# ai_robocarpi_linesensor.net
KiCad netlist of a schematic drawn in EAGLE
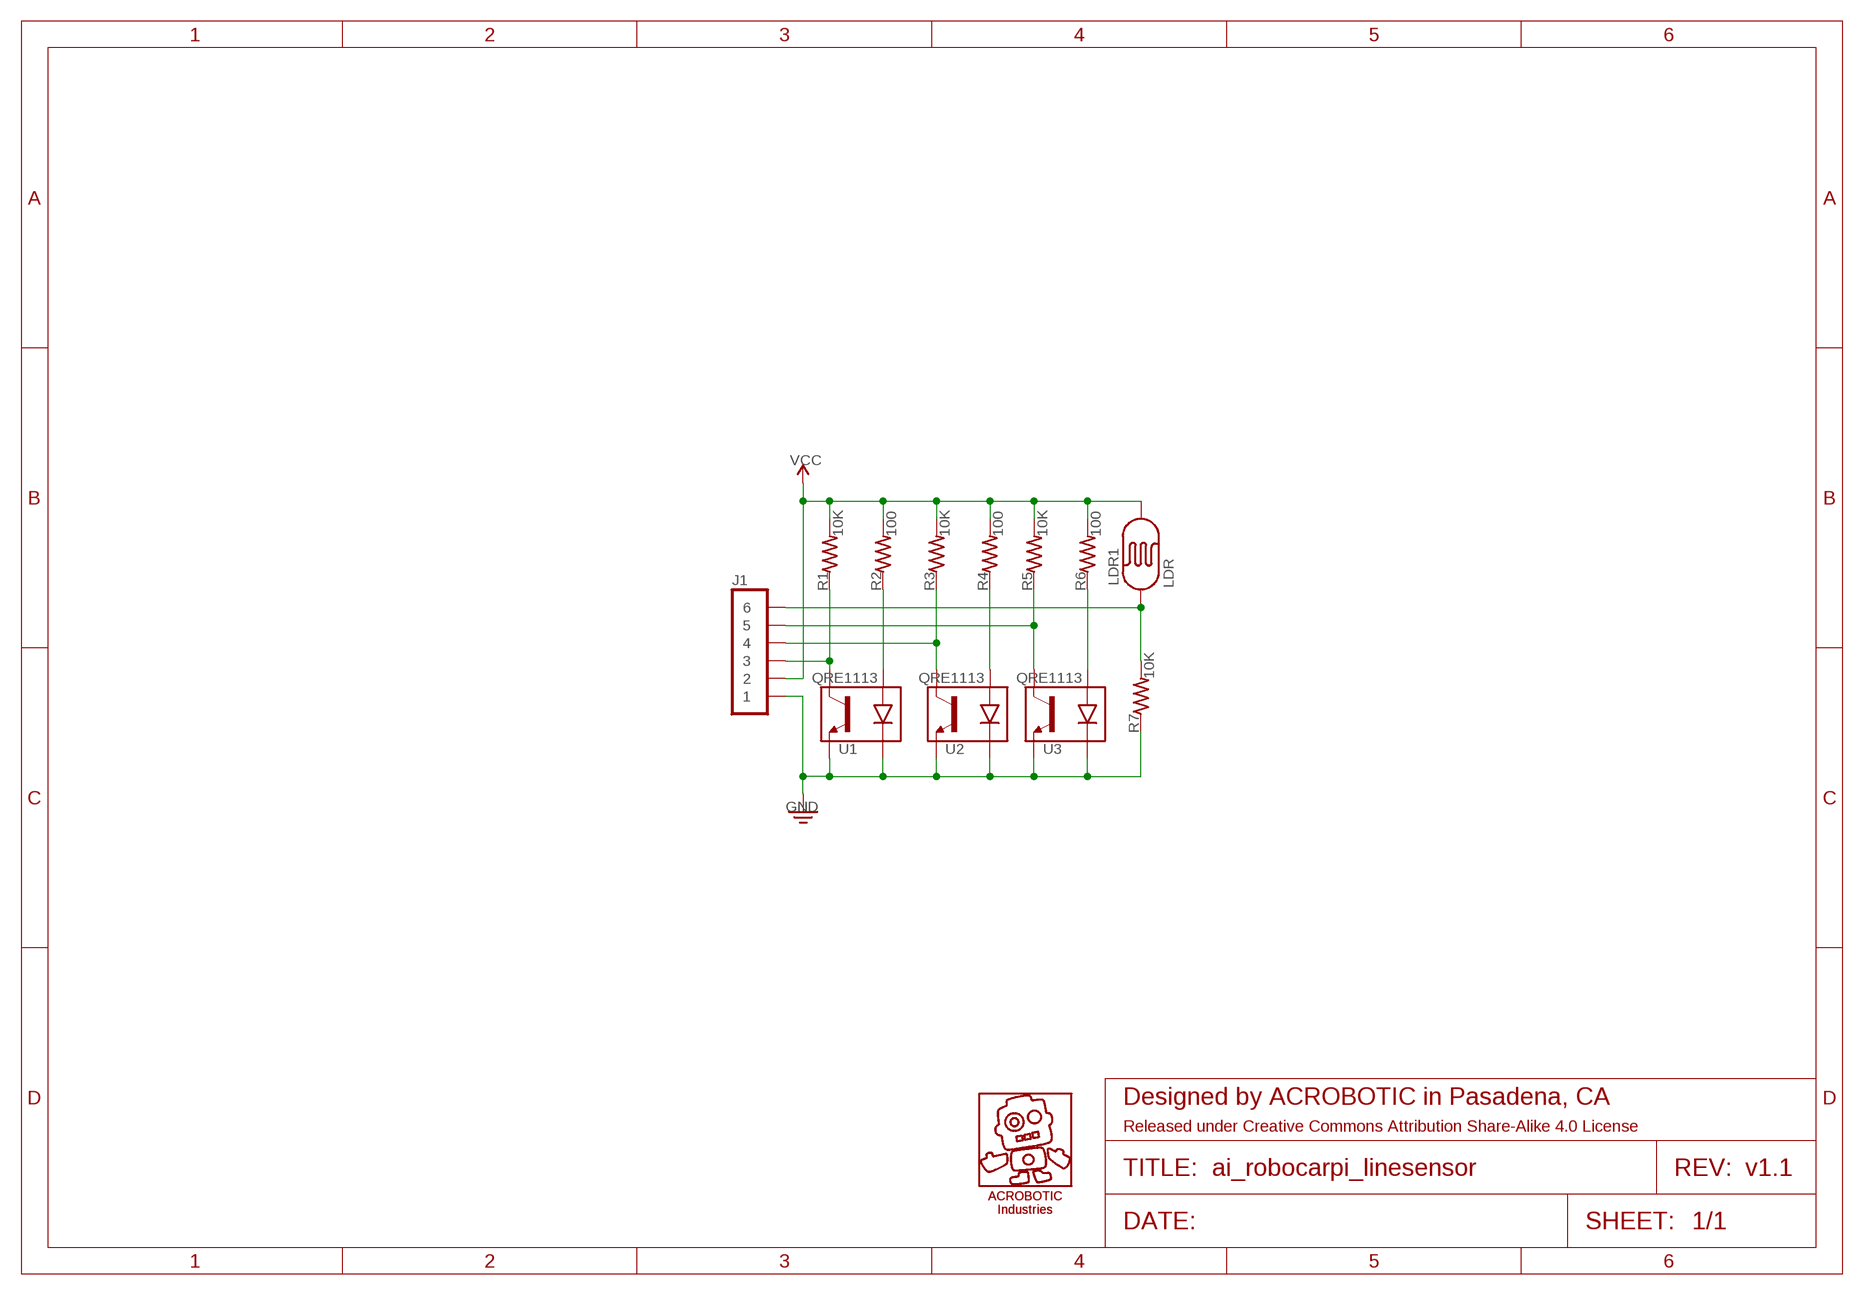
[diagram p0: schematic, sheet 1]

(export (version "E")
  (design (tool "Eeschema 10.0.6"))
  (components
    (comp (ref "FRAME1")
      (value "FRAME-LETTER")
      (footprint "eagle-import:CREATIVE-COMMONS")
      (fields (field (name "REV") "v1.1"))
      (libsource (lib "eagle-import") (part "FRAME-LETTER"))
    )
    (comp (ref "J1")
      (value "1X06")
      (footprint "eagle-import:1X06")
      (libsource (lib "eagle-import") (part "1X06"))
    )
    (comp (ref "LDR1")
      (value "LDR-PTH")
      (footprint "eagle-import:LDR")
      (libsource (lib "eagle-import") (part "LDR-PTH"))
    )
    (comp (ref "R1")
      (value "10K")
      (footprint "eagle-import:RES-0603")
      (libsource (lib "eagle-import") (part "RES0603"))
    )
    (comp (ref "R2")
      (value "100")
      (footprint "eagle-import:RES-0603")
      (libsource (lib "eagle-import") (part "RES0603"))
    )
    (comp (ref "R3")
      (value "10K")
      (footprint "eagle-import:RES-0603")
      (libsource (lib "eagle-import") (part "RES0603"))
    )
    (comp (ref "R4")
      (value "100")
      (footprint "eagle-import:RES-0603")
      (libsource (lib "eagle-import") (part "RES0603"))
    )
    (comp (ref "R5")
      (value "10K")
      (footprint "eagle-import:RES-0603")
      (libsource (lib "eagle-import") (part "RES0603"))
    )
    (comp (ref "R6")
      (value "100")
      (footprint "eagle-import:RES-0603")
      (libsource (lib "eagle-import") (part "RES0603"))
    )
    (comp (ref "R7")
      (value "10K")
      (footprint "eagle-import:RES-0603")
      (libsource (lib "eagle-import") (part "RES0603"))
    )
    (comp (ref "U$4")
      (value "AI-LOGOXS")
      (footprint "eagle-import:AI-LOGO-XS")
      (libsource (lib "eagle-import") (part "AI-LOGOXS"))
    )
    (comp (ref "U$5")
      (value "AI-LOGOXS")
      (footprint "eagle-import:AI-LOGO-XS")
      (libsource (lib "eagle-import") (part "AI-LOGOXS"))
    )
    (comp (ref "U1")
      (value "QRE1113")
      (footprint "eagle-import:QRE1113")
      (libsource (lib "eagle-import") (part "QRE1113"))
    )
    (comp (ref "U2")
      (value "QRE1113")
      (footprint "eagle-import:QRE1113")
      (libsource (lib "eagle-import") (part "QRE1113"))
    )
    (comp (ref "U3")
      (value "QRE1113")
      (footprint "eagle-import:QRE1113")
      (libsource (lib "eagle-import") (part "QRE1113"))
    )
  )
  (nets
    (net (code "1") (name "GND") (class "Default")
      (node (ref "J1") (pin "1") (pinfunction "1_1") (pintype "bidirectional"))
      (node (ref "R7") (pin "1") (pinfunction "1_1") (pintype "passive"))
      (node (ref "U1") (pin "2") (pinfunction "CA_2") (pintype "bidirectional"))
      (node (ref "U1") (pin "4") (pinfunction "E_4") (pintype "bidirectional"))
      (node (ref "U2") (pin "2") (pinfunction "CA_2") (pintype "bidirectional"))
      (node (ref "U2") (pin "4") (pinfunction "E_4") (pintype "bidirectional"))
      (node (ref "U3") (pin "2") (pinfunction "CA_2") (pintype "bidirectional"))
      (node (ref "U3") (pin "4") (pinfunction "E_4") (pintype "bidirectional"))
    )
    (net (code "2") (name "Net-(LDR1-P$1)") (class "Default")
      (node (ref "J1") (pin "6") (pinfunction "6_6") (pintype "bidirectional"))
      (node (ref "LDR1") (pin "1") (pinfunction "P$1_1") (pintype "bidirectional"))
      (node (ref "R7") (pin "2") (pinfunction "2_2") (pintype "passive"))
    )
    (net (code "3") (name "Net-(U1-A)") (class "Default")
      (node (ref "R2") (pin "1") (pinfunction "1_1") (pintype "passive"))
      (node (ref "U1") (pin "1") (pinfunction "A_1") (pintype "bidirectional"))
    )
    (net (code "4") (name "Net-(U1-CO)") (class "Default")
      (node (ref "J1") (pin "3") (pinfunction "3_3") (pintype "bidirectional"))
      (node (ref "R1") (pin "1") (pinfunction "1_1") (pintype "passive"))
      (node (ref "U1") (pin "3") (pinfunction "CO_3") (pintype "bidirectional"))
    )
    (net (code "5") (name "Net-(U2-A)") (class "Default")
      (node (ref "R4") (pin "1") (pinfunction "1_1") (pintype "passive"))
      (node (ref "U2") (pin "1") (pinfunction "A_1") (pintype "bidirectional"))
    )
    (net (code "6") (name "Net-(U2-CO)") (class "Default")
      (node (ref "J1") (pin "4") (pinfunction "4_4") (pintype "bidirectional"))
      (node (ref "R3") (pin "1") (pinfunction "1_1") (pintype "passive"))
      (node (ref "U2") (pin "3") (pinfunction "CO_3") (pintype "bidirectional"))
    )
    (net (code "7") (name "Net-(U3-A)") (class "Default")
      (node (ref "R6") (pin "1") (pinfunction "1_1") (pintype "passive"))
      (node (ref "U3") (pin "1") (pinfunction "A_1") (pintype "bidirectional"))
    )
    (net (code "8") (name "Net-(U3-CO)") (class "Default")
      (node (ref "J1") (pin "5") (pinfunction "5_5") (pintype "bidirectional"))
      (node (ref "R5") (pin "1") (pinfunction "1_1") (pintype "passive"))
      (node (ref "U3") (pin "3") (pinfunction "CO_3") (pintype "bidirectional"))
    )
    (net (code "9") (name "VCC") (class "Default")
      (node (ref "J1") (pin "2") (pinfunction "2_2") (pintype "bidirectional"))
      (node (ref "LDR1") (pin "2") (pinfunction "P$2_2") (pintype "bidirectional"))
      (node (ref "R1") (pin "2") (pinfunction "2_2") (pintype "passive"))
      (node (ref "R2") (pin "2") (pinfunction "2_2") (pintype "passive"))
      (node (ref "R3") (pin "2") (pinfunction "2_2") (pintype "passive"))
      (node (ref "R4") (pin "2") (pinfunction "2_2") (pintype "passive"))
      (node (ref "R5") (pin "2") (pinfunction "2_2") (pintype "passive"))
      (node (ref "R6") (pin "2") (pinfunction "2_2") (pintype "passive"))
    )
  )
)
